# HBridgeShield.net
KiCad netlist of a schematic drawn in EAGLE
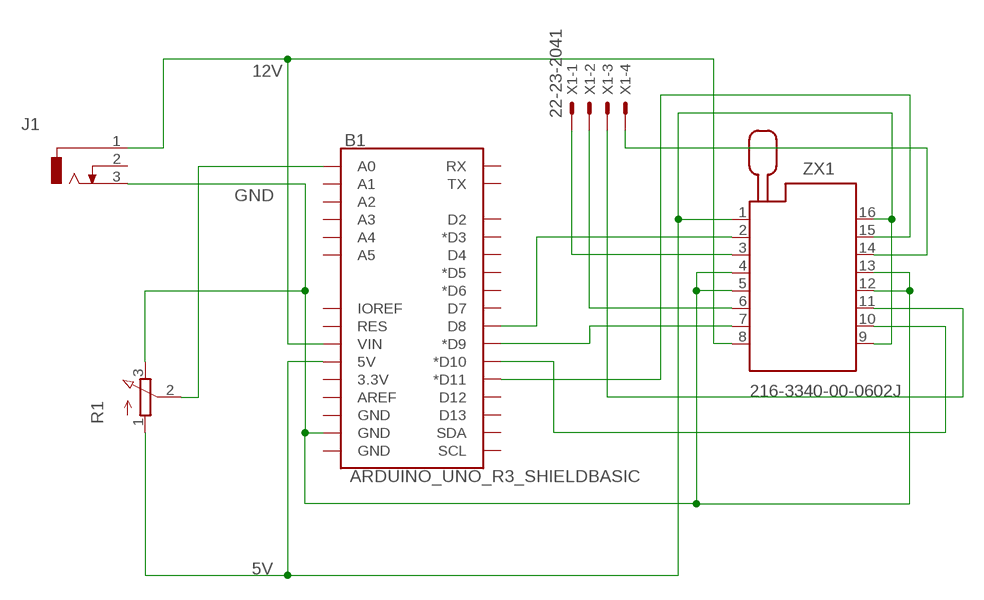
[diagram p0: schematic, sheet 1]

(export (version "E")
  (design (tool "Eeschema 10.0.6"))
  (components
    (comp (ref "B1")
      (value "ARDUINO_UNO_R3_SHIELDBASIC")
      (footprint "eagle-import:UNO_R3_SHIELD")
      (libsource (lib "eagle-import") (part "ARDUINO_UNO_R3_SHIELDBASIC"))
    )
    (comp (ref "J1")
      (value "DCJ0303")
      (footprint "eagle-import:DCJ0303")
      (libsource (lib "eagle-import") (part "DCJ0303"))
    )
    (comp (ref "R1")
      (value "3RP/1610N")
      (footprint "eagle-import:3RP_1610N")
      (libsource (lib "eagle-import") (part "3RP/1610N"))
    )
    (comp (ref "X1")
      (value "22-23-2041")
      (footprint "eagle-import:22-23-2041")
      (fields (field (name "MF") "MOLEX"))
      (libsource (lib "eagle-import") (part "22-23-2041"))
    )
    (comp (ref "ZX1")
      (value "216-3340-00-0602J")
      (footprint "eagle-import:216-3340-00-0602J")
      (fields (field (name "MF") "3M"))
      (libsource (lib "eagle-import") (part "216-3340-00-0602J"))
    )
  )
  (nets
    (net (code "1") (name "/5V") (class "Default")
      (node (ref "B1") (pin "5V") (pinfunction "5V_5V") (pintype "bidirectional"))
      (node (ref "R1") (pin "1") (pinfunction "A_1") (pintype "passive"))
      (node (ref "ZX1") (pin "1") (pinfunction "1_1") (pintype "passive"))
      (node (ref "ZX1") (pin "16") (pinfunction "16_16") (pintype "passive"))
      (node (ref "ZX1") (pin "9") (pinfunction "9_9") (pintype "passive"))
    )
    (net (code "2") (name "/12V") (class "Default")
      (node (ref "B1") (pin "VIN") (pinfunction "VIN_VIN") (pintype "bidirectional"))
      (node (ref "J1") (pin "1") (pinfunction "1_1") (pintype "passive"))
      (node (ref "ZX1") (pin "8") (pinfunction "8_8") (pintype "passive"))
    )
    (net (code "3") (name "/GND") (class "Default")
      (node (ref "B1") (pin "GND@1") (pinfunction "GND_GND@1") (pintype "bidirectional"))
      (node (ref "J1") (pin "3") (pinfunction "3_3") (pintype "passive"))
      (node (ref "R1") (pin "3") (pinfunction "E_3") (pintype "passive"))
      (node (ref "ZX1") (pin "12") (pinfunction "12_12") (pintype "passive"))
      (node (ref "ZX1") (pin "13") (pinfunction "13_13") (pintype "passive"))
      (node (ref "ZX1") (pin "4") (pinfunction "4_4") (pintype "passive"))
      (node (ref "ZX1") (pin "5") (pinfunction "5_5") (pintype "passive"))
    )
    (net (code "4") (name "Net-(B1-*D9)") (class "Default")
      (node (ref "B1") (pin "D9") (pinfunction "*D9_D9") (pintype "bidirectional"))
      (node (ref "ZX1") (pin "7") (pinfunction "7_7") (pintype "passive"))
    )
    (net (code "5") (name "Net-(B1-*D10)") (class "Default")
      (node (ref "B1") (pin "D10") (pinfunction "*D10_D10") (pintype "bidirectional"))
      (node (ref "ZX1") (pin "10") (pinfunction "10_10") (pintype "passive"))
    )
    (net (code "6") (name "Net-(B1-*D11)") (class "Default")
      (node (ref "B1") (pin "D11") (pinfunction "*D11_D11") (pintype "bidirectional"))
      (node (ref "ZX1") (pin "15") (pinfunction "15_15") (pintype "passive"))
    )
    (net (code "7") (name "Net-(B1-PadD8)") (class "Default")
      (node (ref "B1") (pin "D8") (pinfunction "D8_D8") (pintype "bidirectional"))
      (node (ref "ZX1") (pin "2") (pinfunction "2_2") (pintype "passive"))
    )
    (net (code "8") (name "Net-(R1-S)") (class "Default")
      (node (ref "B1") (pin "A0") (pinfunction "A0_A0") (pintype "bidirectional"))
      (node (ref "R1") (pin "2") (pinfunction "S_2") (pintype "passive"))
    )
    (net (code "9") (name "Net-(X1A-S)") (class "Default")
      (node (ref "X1") (pin "1") (pinfunction "S_1") (pintype "passive"))
      (node (ref "ZX1") (pin "3") (pinfunction "3_3") (pintype "passive"))
    )
    (net (code "10") (name "Net-(X1B-S)") (class "Default")
      (node (ref "X1") (pin "2") (pinfunction "S_2") (pintype "passive"))
      (node (ref "ZX1") (pin "6") (pinfunction "6_6") (pintype "passive"))
    )
    (net (code "11") (name "Net-(X1C-S)") (class "Default")
      (node (ref "X1") (pin "3") (pinfunction "S_3") (pintype "passive"))
      (node (ref "ZX1") (pin "11") (pinfunction "11_11") (pintype "passive"))
    )
    (net (code "12") (name "Net-(X1D-S)") (class "Default")
      (node (ref "X1") (pin "4") (pinfunction "S_4") (pintype "passive"))
      (node (ref "ZX1") (pin "14") (pinfunction "14_14") (pintype "passive"))
    )
    (net (code "13") (name "unconnected-(B1-*D3-PadD3)") (class "Default")
      (node (ref "B1") (pin "D3") (pinfunction "*D3_D3") (pintype "bidirectional"))
    )
    (net (code "14") (name "unconnected-(B1-*D5-PadD5)") (class "Default")
      (node (ref "B1") (pin "D5") (pinfunction "*D5_D5") (pintype "bidirectional"))
    )
    (net (code "15") (name "unconnected-(B1-*D6-PadD6)") (class "Default")
      (node (ref "B1") (pin "D6") (pinfunction "*D6_D6") (pintype "bidirectional"))
    )
    (net (code "16") (name "unconnected-(B1-GND-PadGND@0)") (class "Default")
      (node (ref "B1") (pin "GND@0") (pinfunction "GND_GND@0") (pintype "bidirectional"))
    )
    (net (code "17") (name "unconnected-(B1-GND-PadGND@2)") (class "Default")
      (node (ref "B1") (pin "GND@2") (pinfunction "GND_GND@2") (pintype "bidirectional"))
    )
    (net (code "18") (name "unconnected-(B1-Pad3.3V)") (class "Default")
      (node (ref "B1") (pin "3.3V") (pinfunction "3.3V_3.3V") (pintype "bidirectional"))
    )
    (net (code "19") (name "unconnected-(B1-PadA1)") (class "Default")
      (node (ref "B1") (pin "A1") (pinfunction "A1_A1") (pintype "bidirectional"))
    )
    (net (code "20") (name "unconnected-(B1-PadA2)") (class "Default")
      (node (ref "B1") (pin "A2") (pinfunction "A2_A2") (pintype "bidirectional"))
    )
    (net (code "21") (name "unconnected-(B1-PadA3)") (class "Default")
      (node (ref "B1") (pin "A3") (pinfunction "A3_A3") (pintype "bidirectional"))
    )
    (net (code "22") (name "unconnected-(B1-PadA4)") (class "Default")
      (node (ref "B1") (pin "A4") (pinfunction "A4_A4") (pintype "bidirectional"))
    )
    (net (code "23") (name "unconnected-(B1-PadA5)") (class "Default")
      (node (ref "B1") (pin "A5") (pinfunction "A5_A5") (pintype "bidirectional"))
    )
    (net (code "24") (name "unconnected-(B1-PadAREF)") (class "Default")
      (node (ref "B1") (pin "AREF") (pinfunction "AREF_AREF") (pintype "bidirectional"))
    )
    (net (code "25") (name "unconnected-(B1-PadD2)") (class "Default")
      (node (ref "B1") (pin "D2") (pinfunction "D2_D2") (pintype "bidirectional"))
    )
    (net (code "26") (name "unconnected-(B1-PadD4)") (class "Default")
      (node (ref "B1") (pin "D4") (pinfunction "D4_D4") (pintype "bidirectional"))
    )
    (net (code "27") (name "unconnected-(B1-PadD7)") (class "Default")
      (node (ref "B1") (pin "D7") (pinfunction "D7_D7") (pintype "bidirectional"))
    )
    (net (code "28") (name "unconnected-(B1-PadD12)") (class "Default")
      (node (ref "B1") (pin "D12") (pinfunction "D12_D12") (pintype "bidirectional"))
    )
    (net (code "29") (name "unconnected-(B1-PadD13)") (class "Default")
      (node (ref "B1") (pin "D13") (pinfunction "D13_D13") (pintype "bidirectional"))
    )
    (net (code "30") (name "unconnected-(B1-PadIOREF)") (class "Default")
      (node (ref "B1") (pin "IOREF") (pinfunction "IOREF_IOREF") (pintype "bidirectional"))
    )
    (net (code "31") (name "unconnected-(B1-PadRES)") (class "Default")
      (node (ref "B1") (pin "RES") (pinfunction "RES_RES") (pintype "bidirectional"))
    )
    (net (code "32") (name "unconnected-(B1-PadRX)") (class "Default")
      (node (ref "B1") (pin "RX") (pinfunction "RX_RX") (pintype "bidirectional"))
    )
    (net (code "33") (name "unconnected-(B1-PadSCL)") (class "Default")
      (node (ref "B1") (pin "SCL") (pinfunction "SCL_SCL") (pintype "bidirectional"))
    )
    (net (code "34") (name "unconnected-(B1-PadSDA)") (class "Default")
      (node (ref "B1") (pin "SDA") (pinfunction "SDA_SDA") (pintype "bidirectional"))
    )
    (net (code "35") (name "unconnected-(B1-PadTX)") (class "Default")
      (node (ref "B1") (pin "TX") (pinfunction "TX_TX") (pintype "bidirectional"))
    )
    (net (code "36") (name "unconnected-(J1-Pad2)") (class "Default")
      (node (ref "J1") (pin "2") (pinfunction "2_2") (pintype "passive"))
    )
  )
)
